# SideSense.net
KiCad netlist of a schematic drawn in Altium Designer
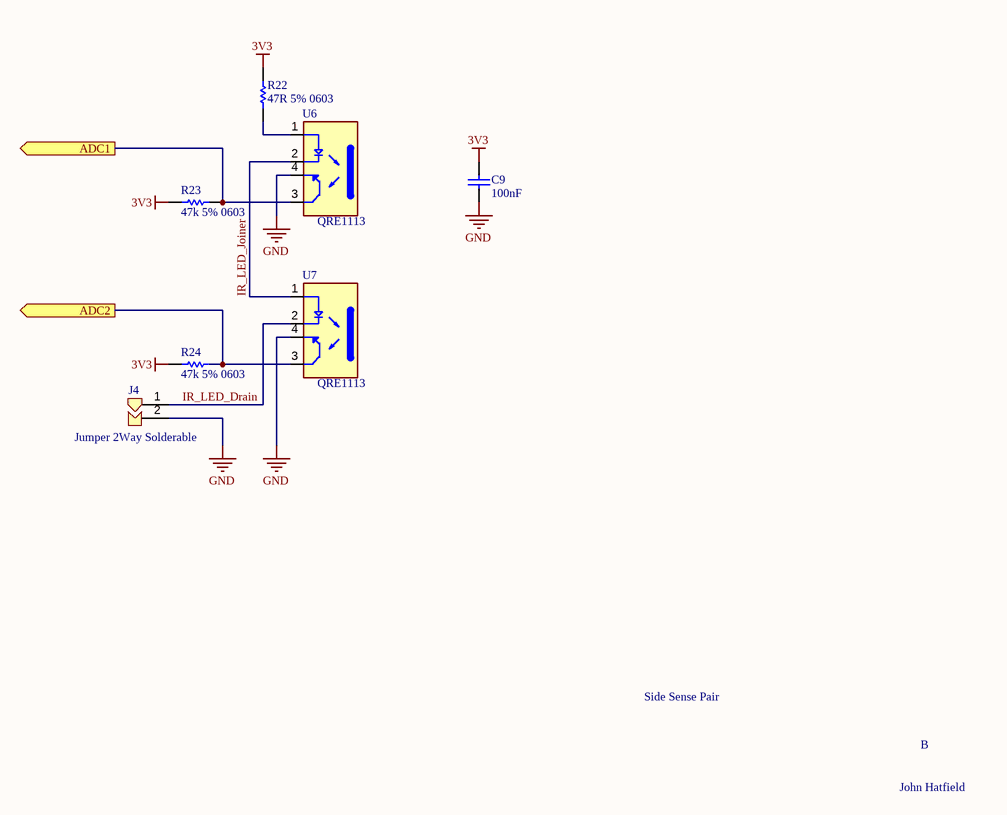
[diagram p0: SideSense.SchDoc]

(export (version "E")
  (design (tool "Eeschema 10.0.6"))
  (components
    (comp (ref "C9")
      (value "100nF")
      (footprint "Cap_Ceramic_0603")
      (description "Capacitor, Ceramic, SMD, 100nF, 50V, 5%, X7R, 0603")
      (libsource (lib "StandardCapacitors") (part "100nF 50V 5% X7R 0603"))
    )
    (comp (ref "J4")
      (value "Jumper 2Way Solderable")
      (footprint "Jumper_2Way_Solderable")
      (description "Jumper 2Way Side Solderable")
      (libsource (lib "QUTMS_JumperLibrary") (part "Jumper 2Way Side Solderable"))
    )
    (comp (ref "R22")
      (value "47R 5% 0603")
      (footprint "Res_ThinFilm_0603")
      (description "Resistor, SMD, 47R, 0.1W, 5%, 0603")
      (libsource (lib "StandardResistors") (part "47R 5% 0603"))
    )
    (comp (ref "R23")
      (value "47k 5% 0603")
      (footprint "Res_ThinFilm_0603")
      (description "Resistor, SMD, 47k, 0.1W, 5%, 0603")
      (libsource (lib "StandardResistors") (part "47k 5% 0603"))
    )
    (comp (ref "R24")
      (value "47k 5% 0603")
      (footprint "Res_ThinFilm_0603")
      (description "Resistor, SMD, 47k, 0.1W, 5%, 0603")
      (libsource (lib "StandardResistors") (part "47k 5% 0603"))
    )
    (comp (ref "U6")
      (value "QRE1113")
      (footprint "DIP400W50P180L360H200Q4")
      (description "Reflective Optical Sensor 0.197 _5mm_ 4-DIP _0.157, 4.00mm_")
      (fields (field (name "MF") "ON Semiconductor"))
      (libsource (lib "QRE1113") (part "QRE1113"))
    )
    (comp (ref "U7")
      (value "QRE1113")
      (footprint "DIP400W50P180L360H200Q4")
      (description "Reflective Optical Sensor 0.197 _5mm_ 4-DIP _0.157, 4.00mm_")
      (fields (field (name "MF") "ON Semiconductor"))
      (libsource (lib "QRE1113") (part "QRE1113"))
    )
  )
  (nets
    (net (code "1") (name "/ADC1") (class "Default")
      (node (ref "R23") (pin "2") (pinfunction "2_2") (pintype "passive"))
      (node (ref "U6") (pin "3") (pinfunction "CT_3") (pintype "passive"))
    )
    (net (code "2") (name "/ADC2") (class "Default")
      (node (ref "R24") (pin "2") (pinfunction "2_2") (pintype "passive"))
      (node (ref "U7") (pin "3") (pinfunction "CT_3") (pintype "passive"))
    )
    (net (code "3") (name "/IR_LED_Drain") (class "Default")
      (node (ref "J4") (pin "1") (pinfunction "1_1") (pintype "passive"))
      (node (ref "U7") (pin "2") (pinfunction "C_2") (pintype "passive"))
    )
    (net (code "4") (name "/IR_LED_Joiner") (class "Default")
      (node (ref "U6") (pin "2") (pinfunction "C_2") (pintype "passive"))
      (node (ref "U7") (pin "1") (pinfunction "A_1") (pintype "passive"))
    )
    (net (code "5") (name "3V3") (class "Default")
      (node (ref "C9") (pin "2") (pinfunction "2_2") (pintype "passive"))
      (node (ref "R22") (pin "2") (pinfunction "2_2") (pintype "passive"))
      (node (ref "R23") (pin "1") (pinfunction "1_1") (pintype "passive"))
      (node (ref "R24") (pin "1") (pinfunction "1_1") (pintype "passive"))
    )
    (net (code "6") (name "GND") (class "Default")
      (node (ref "C9") (pin "1") (pinfunction "1_1") (pintype "passive"))
      (node (ref "J4") (pin "2") (pinfunction "2_2") (pintype "passive"))
      (node (ref "U6") (pin "4") (pinfunction "ET_4") (pintype "passive"))
      (node (ref "U7") (pin "4") (pinfunction "ET_4") (pintype "passive"))
    )
    (net (code "7") (name "Net-(U6-A)") (class "Default")
      (node (ref "R22") (pin "1") (pinfunction "1_1") (pintype "passive"))
      (node (ref "U6") (pin "1") (pinfunction "A_1") (pintype "passive"))
    )
  )
)
